# Sheet1.net
KiCad netlist of a schematic drawn in Altium Designer
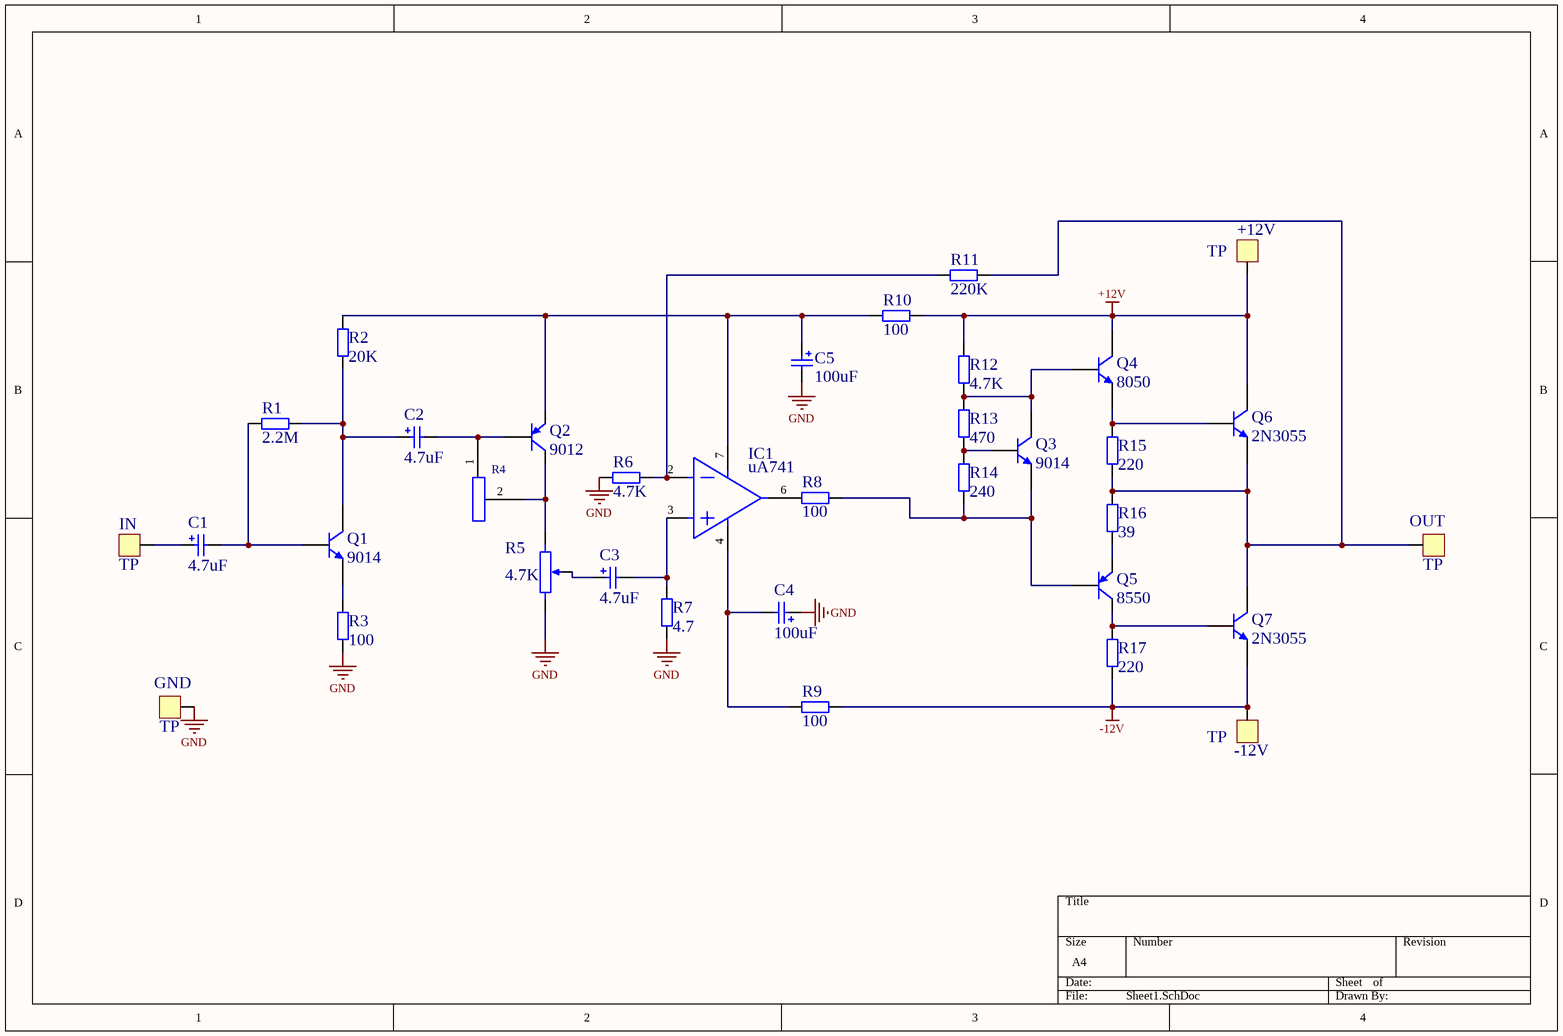
[diagram p0: Sheet1.SchDoc]

(export (version "E")
  (design (tool "Eeschema 10.0.6"))
  (components
    (comp (ref "+12V") (value "TP") (footprint "TP2") (libsource (lib "") (part "TP_3")))
    (comp (ref "-12V") (value "TP") (footprint "TP2") (libsource (lib "") (part "TP_2")))
    (comp (ref "C1")
      (value "4.7uF")
      (footprint "CAPPR5-5x5")
      (description "Polarized Capacitor (Axial)")
      (fields (field (name "Comment") "Cap Pol2") (field (name "PUBLISHER") "Altium Limited"))
      (libsource (lib "teach2018") (part "Cap Pol2"))
    )
    (comp (ref "C2")
      (value "4.7uF")
      (footprint "CAPPR5-5x5")
      (description "Polarized Capacitor (Axial)")
      (fields (field (name "Comment") "Cap Pol2") (field (name "PUBLISHER") "Altium Limited"))
      (libsource (lib "teach2018") (part "Cap Pol2"))
    )
    (comp (ref "C3")
      (value "4.7uF")
      (footprint "CAPPR5-5x5")
      (description "Polarized Capacitor (Axial)")
      (fields (field (name "Comment") "Cap Pol2") (field (name "PUBLISHER") "Altium Limited"))
      (libsource (lib "teach2018") (part "Cap Pol2"))
    )
    (comp (ref "C4")
      (value "100uF")
      (footprint "CAPPR5-5x5")
      (description "Polarized Capacitor (Axial)")
      (fields (field (name "Comment") "Cap Pol2") (field (name "PUBLISHER") "Altium Limited"))
      (libsource (lib "teach2018") (part "Cap Pol2"))
    )
    (comp (ref "C5")
      (value "100uF")
      (footprint "CAPPR5-5x5")
      (description "Polarized Capacitor (Axial)")
      (fields (field (name "Comment") "Cap Pol2") (field (name "PUBLISHER") "Altium Limited"))
      (libsource (lib "teach2018") (part "Cap Pol2"))
    )
    (comp (ref "GND") (value "TP") (footprint "TP2") (libsource (lib "teach2018") (part "TP")))
    (comp (ref "IC1")
      (value "uA741")
      (footprint "DIP8")
      (description "OAP")
      (libsource (lib "teach2018") (part "uA741"))
    )
    (comp (ref "IN") (value "TP") (footprint "TP2") (libsource (lib "teach2018") (part "TP")))
    (comp (ref "OUT") (value "TP") (footprint "TP2") (libsource (lib "") (part "TP_1")))
    (comp (ref "Q1")
      (value "9014")
      (footprint "TANS")
      (description "NPN General Purpose Amplifier")
      (fields (field (name "PUBLISHER") "Altium Limited"))
      (libsource (lib "teach2018") (part "2N3904"))
    )
    (comp (ref "Q2")
      (value "9012")
      (footprint "TANS")
      (description "PNP Transistor")
      (libsource (lib "teach2018") (part "9012"))
    )
    (comp (ref "Q3")
      (value "9014")
      (footprint "TANS")
      (description "NPN General Purpose Amplifier")
      (fields (field (name "PUBLISHER") "Altium Limited"))
      (libsource (lib "teach2018") (part "2N3904"))
    )
    (comp (ref "Q4")
      (value "8050")
      (footprint "TANS")
      (description "NPN General Purpose Amplifier")
      (fields (field (name "PUBLISHER") "Altium Limited"))
      (libsource (lib "teach2018") (part "8050"))
    )
    (comp (ref "Q5")
      (value "8550")
      (footprint "TANS")
      (description "PNP Transistor")
      (libsource (lib "teach2018") (part "8550"))
    )
    (comp (ref "Q6")
      (value "2N3055")
      (footprint "TO-3")
      (description "NPN General Purpose Amplifier")
      (fields (field (name "PUBLISHER") "Altium Limited"))
      (libsource (lib "teach2018") (part "2N3055"))
    )
    (comp (ref "Q7")
      (value "2N3055")
      (footprint "TO-3")
      (description "NPN General Purpose Amplifier")
      (fields (field (name "PUBLISHER") "Altium Limited"))
      (libsource (lib "teach2018") (part "2N3055"))
    )
    (comp (ref "R1")
      (value "2.2M")
      (footprint "AXIAL-0.4")
      (description "Resistor")
      (fields (field (name "Comment") "Res2") (field (name "PUBLISHER") "Altium Limited"))
      (libsource (lib "") (part "Res2_1"))
    )
    (comp (ref "R2")
      (value "20K")
      (footprint "AXIAL-0.4")
      (description "Resistor")
      (fields (field (name "Comment") "Res2") (field (name "PUBLISHER") "Altium Limited"))
      (libsource (lib "teach2018") (part "Res2"))
    )
    (comp (ref "R3")
      (value "100")
      (footprint "AXIAL-0.4")
      (description "Resistor")
      (fields (field (name "Comment") "Res2") (field (name "PUBLISHER") "Altium Limited"))
      (libsource (lib "teach2018") (part "Res2"))
    )
    (comp (ref "R4")
      (value "vari-Res")
      (footprint "vari-Res")
      (libsource (lib "teach2018") (part "vari-Res"))
    )
    (comp (ref "R5")
      (value "4.7K")
      (footprint "RPOT")
      (description "Potentiometer")
      (fields (field (name "Comment") "RPOT"))
      (libsource (lib "teach2018") (part "RPOT"))
    )
    (comp (ref "R6")
      (value "4.7K")
      (footprint "AXIAL-0.4")
      (description "Resistor")
      (fields (field (name "Comment") "Res2") (field (name "PUBLISHER") "Altium Limited"))
      (libsource (lib "") (part "Res2_1"))
    )
    (comp (ref "R7")
      (value "4.7")
      (footprint "AXIAL-0.4")
      (description "Resistor")
      (fields (field (name "Comment") "Res2") (field (name "PUBLISHER") "Altium Limited"))
      (libsource (lib "teach2018") (part "Res2"))
    )
    (comp (ref "R8")
      (value "100")
      (footprint "AXIAL-0.4")
      (description "Resistor")
      (fields (field (name "Comment") "Res2") (field (name "PUBLISHER") "Altium Limited"))
      (libsource (lib "") (part "Res2_1"))
    )
    (comp (ref "R9")
      (value "100")
      (footprint "AXIAL-0.4")
      (description "Resistor")
      (fields (field (name "Comment") "Res2") (field (name "PUBLISHER") "Altium Limited"))
      (libsource (lib "") (part "Res2_1"))
    )
    (comp (ref "R10")
      (value "100")
      (footprint "AXIAL-0.4")
      (description "Resistor")
      (fields (field (name "Comment") "Res2") (field (name "PUBLISHER") "Altium Limited"))
      (libsource (lib "") (part "Res2_1"))
    )
    (comp (ref "R11")
      (value "220K")
      (footprint "AXIAL-0.4")
      (description "Resistor")
      (fields (field (name "Comment") "Res2") (field (name "PUBLISHER") "Altium Limited"))
      (libsource (lib "") (part "Res2_1"))
    )
    (comp (ref "R12")
      (value "4.7K")
      (footprint "AXIAL-0.4")
      (description "Resistor")
      (fields (field (name "Comment") "Res2") (field (name "PUBLISHER") "Altium Limited"))
      (libsource (lib "teach2018") (part "Res2"))
    )
    (comp (ref "R13")
      (value "470")
      (footprint "AXIAL-0.4")
      (description "Resistor")
      (fields (field (name "Comment") "Res2") (field (name "PUBLISHER") "Altium Limited"))
      (libsource (lib "teach2018") (part "Res2"))
    )
    (comp (ref "R14")
      (value "240")
      (footprint "AXIAL-0.4")
      (description "Resistor")
      (fields (field (name "Comment") "Res2") (field (name "PUBLISHER") "Altium Limited"))
      (libsource (lib "teach2018") (part "Res2"))
    )
    (comp (ref "R15")
      (value "220")
      (footprint "AXIAL-0.4")
      (description "Resistor")
      (fields (field (name "Comment") "Res2") (field (name "PUBLISHER") "Altium Limited"))
      (libsource (lib "teach2018") (part "Res2"))
    )
    (comp (ref "R16")
      (value "39")
      (footprint "AXIAL-0.4")
      (description "Resistor")
      (fields (field (name "Comment") "Res2") (field (name "PUBLISHER") "Altium Limited"))
      (libsource (lib "teach2018") (part "Res2"))
    )
    (comp (ref "R17")
      (value "220")
      (footprint "AXIAL-0.4")
      (description "Resistor")
      (fields (field (name "Comment") "Res2") (field (name "PUBLISHER") "Altium Limited"))
      (libsource (lib "teach2018") (part "Res2"))
    )
  )
  (nets
    (net (code "1") (name "+12V") (class "Default")
      (node (ref "+12V") (pin "1") (pinfunction "1_1") (pintype "passive"))
      (node (ref "Q4") (pin "3") (pinfunction "C_3") (pintype "passive"))
      (node (ref "Q6") (pin "3") (pinfunction "C_3") (pintype "passive"))
      (node (ref "R10") (pin "2") (pinfunction "2_2") (pintype "passive"))
      (node (ref "R12") (pin "2") (pinfunction "2_2") (pintype "passive"))
    )
    (net (code "2") (name "-12V") (class "Default")
      (node (ref "-12V") (pin "1") (pinfunction "1_1") (pintype "passive"))
      (node (ref "Q7") (pin "2") (pinfunction "E_2") (pintype "passive"))
      (node (ref "R17") (pin "1") (pinfunction "1_1") (pintype "passive"))
      (node (ref "R9") (pin "2") (pinfunction "2_2") (pintype "passive"))
    )
    (net (code "3") (name "1") (class "Default")
      (node (ref "IC1") (pin "1") (pinfunction "1_1") (pintype "passive"))
    )
    (net (code "4") (name "8") (class "Default")
      (node (ref "IC1") (pin "8") (pinfunction "8_8") (pintype "passive"))
    )
    (net (code "5") (name "GND") (class "Default")
      (node (ref "C4") (pin "1") (pinfunction "1_1") (pintype "passive"))
      (node (ref "C5") (pin "2") (pinfunction "2_2") (pintype "passive"))
      (node (ref "GND") (pin "1") (pinfunction "1_1") (pintype "passive"))
      (node (ref "R3") (pin "1") (pinfunction "1_1") (pintype "passive"))
      (node (ref "R5") (pin "3") (pinfunction "BOT_3") (pintype "passive"))
      (node (ref "R6") (pin "1") (pinfunction "1_1") (pintype "passive"))
      (node (ref "R7") (pin "1") (pinfunction "1_1") (pintype "passive"))
    )
    (net (code "6") (name "Net-(C1-Pad1)") (class "Default")
      (node (ref "C1") (pin "1") (pinfunction "1_1") (pintype "passive"))
      (node (ref "IN") (pin "1") (pinfunction "1_1") (pintype "passive"))
    )
    (net (code "7") (name "Net-(C3-Pad2)") (class "Default")
      (node (ref "C3") (pin "2") (pinfunction "2_2") (pintype "passive"))
      (node (ref "IC1") (pin "3") (pinfunction "3_3") (pintype "passive"))
      (node (ref "R7") (pin "2") (pinfunction "2_2") (pintype "passive"))
    )
    (net (code "8") (name "Net-(C4-Pad2)") (class "Default")
      (node (ref "C4") (pin "2") (pinfunction "2_2") (pintype "passive"))
      (node (ref "IC1") (pin "4") (pinfunction "4_4") (pintype "passive"))
      (node (ref "R9") (pin "1") (pinfunction "1_1") (pintype "passive"))
    )
    (net (code "9") (name "Net-(IC1-Pad2)") (class "Default")
      (node (ref "IC1") (pin "2") (pinfunction "2_2") (pintype "passive"))
      (node (ref "R11") (pin "1") (pinfunction "1_1") (pintype "passive"))
      (node (ref "R6") (pin "2") (pinfunction "2_2") (pintype "passive"))
    )
    (net (code "10") (name "Net-(IC1-Pad6)") (class "Default")
      (node (ref "IC1") (pin "6") (pinfunction "6_6") (pintype "passive"))
      (node (ref "R8") (pin "1") (pinfunction "1_1") (pintype "passive"))
    )
    (net (code "11") (name "Net-(Q1-B)") (class "Default")
      (node (ref "C1") (pin "2") (pinfunction "2_2") (pintype "passive"))
      (node (ref "Q1") (pin "2") (pinfunction "B_2") (pintype "passive"))
      (node (ref "R1") (pin "1") (pinfunction "1_1") (pintype "passive"))
    )
    (net (code "12") (name "Net-(Q1-C)") (class "Default")
      (node (ref "C2") (pin "1") (pinfunction "1_1") (pintype "passive"))
      (node (ref "Q1") (pin "3") (pinfunction "C_3") (pintype "passive"))
      (node (ref "R1") (pin "2") (pinfunction "2_2") (pintype "passive"))
      (node (ref "R2") (pin "1") (pinfunction "1_1") (pintype "passive"))
    )
    (net (code "13") (name "Net-(Q1-E)") (class "Default")
      (node (ref "Q1") (pin "1") (pinfunction "E_1") (pintype "passive"))
      (node (ref "R3") (pin "2") (pinfunction "2_2") (pintype "passive"))
    )
    (net (code "14") (name "Net-(Q2-B)") (class "Default")
      (node (ref "C2") (pin "2") (pinfunction "2_2") (pintype "passive"))
      (node (ref "Q2") (pin "2") (pinfunction "B_2") (pintype "passive"))
      (node (ref "R4") (pin "1") (pinfunction "TOP_1") (pintype "passive"))
    )
    (net (code "15") (name "Net-(Q2-C)") (class "Default")
      (node (ref "Q2") (pin "3") (pinfunction "C_3") (pintype "passive"))
      (node (ref "R4") (pin "2") (pinfunction "TAP_2") (pintype "passive"))
      (node (ref "R5") (pin "1") (pinfunction "TOP_1") (pintype "passive"))
    )
    (net (code "16") (name "Net-(Q2-E)") (class "Default")
      (node (ref "C5") (pin "1") (pinfunction "1_1") (pintype "passive"))
      (node (ref "IC1") (pin "7") (pinfunction "7_7") (pintype "passive"))
      (node (ref "Q2") (pin "1") (pinfunction "E_1") (pintype "passive"))
      (node (ref "R10") (pin "1") (pinfunction "1_1") (pintype "passive"))
      (node (ref "R2") (pin "2") (pinfunction "2_2") (pintype "passive"))
    )
    (net (code "17") (name "Net-(Q3-B)") (class "Default")
      (node (ref "Q3") (pin "2") (pinfunction "B_2") (pintype "passive"))
      (node (ref "R13") (pin "1") (pinfunction "1_1") (pintype "passive"))
      (node (ref "R14") (pin "2") (pinfunction "2_2") (pintype "passive"))
    )
    (net (code "18") (name "Net-(Q3-C)") (class "Default")
      (node (ref "Q3") (pin "3") (pinfunction "C_3") (pintype "passive"))
      (node (ref "Q4") (pin "2") (pinfunction "B_2") (pintype "passive"))
      (node (ref "R12") (pin "1") (pinfunction "1_1") (pintype "passive"))
      (node (ref "R13") (pin "2") (pinfunction "2_2") (pintype "passive"))
    )
    (net (code "19") (name "Net-(Q3-E)") (class "Default")
      (node (ref "Q3") (pin "1") (pinfunction "E_1") (pintype "passive"))
      (node (ref "Q5") (pin "2") (pinfunction "B_2") (pintype "passive"))
      (node (ref "R14") (pin "1") (pinfunction "1_1") (pintype "passive"))
      (node (ref "R8") (pin "2") (pinfunction "2_2") (pintype "passive"))
    )
    (net (code "20") (name "Net-(Q4-E)") (class "Default")
      (node (ref "Q4") (pin "1") (pinfunction "E_1") (pintype "passive"))
      (node (ref "Q6") (pin "1") (pinfunction "B_1") (pintype "passive"))
      (node (ref "R15") (pin "2") (pinfunction "2_2") (pintype "passive"))
    )
    (net (code "21") (name "Net-(Q5-C)") (class "Default")
      (node (ref "Q5") (pin "3") (pinfunction "C_3") (pintype "passive"))
      (node (ref "Q7") (pin "1") (pinfunction "B_1") (pintype "passive"))
      (node (ref "R17") (pin "2") (pinfunction "2_2") (pintype "passive"))
    )
    (net (code "22") (name "Net-(Q5-E)") (class "Default")
      (node (ref "Q5") (pin "1") (pinfunction "E_1") (pintype "passive"))
      (node (ref "R16") (pin "1") (pinfunction "1_1") (pintype "passive"))
    )
    (net (code "23") (name "Net-(Q6-E)") (class "Default")
      (node (ref "OUT") (pin "1") (pinfunction "1_1") (pintype "passive"))
      (node (ref "Q6") (pin "2") (pinfunction "E_2") (pintype "passive"))
      (node (ref "Q7") (pin "3") (pinfunction "C_3") (pintype "passive"))
      (node (ref "R11") (pin "2") (pinfunction "2_2") (pintype "passive"))
      (node (ref "R15") (pin "1") (pinfunction "1_1") (pintype "passive"))
      (node (ref "R16") (pin "2") (pinfunction "2_2") (pintype "passive"))
    )
    (net (code "24") (name "Net-(R5-TAP)") (class "Default")
      (node (ref "C3") (pin "1") (pinfunction "1_1") (pintype "passive"))
      (node (ref "R5") (pin "2") (pinfunction "TAP_2") (pintype "passive"))
    )
  )
)
